# LockSwitchSchematicEasyEDA.net
KiCad netlist of a schematic drawn in EasyEDA
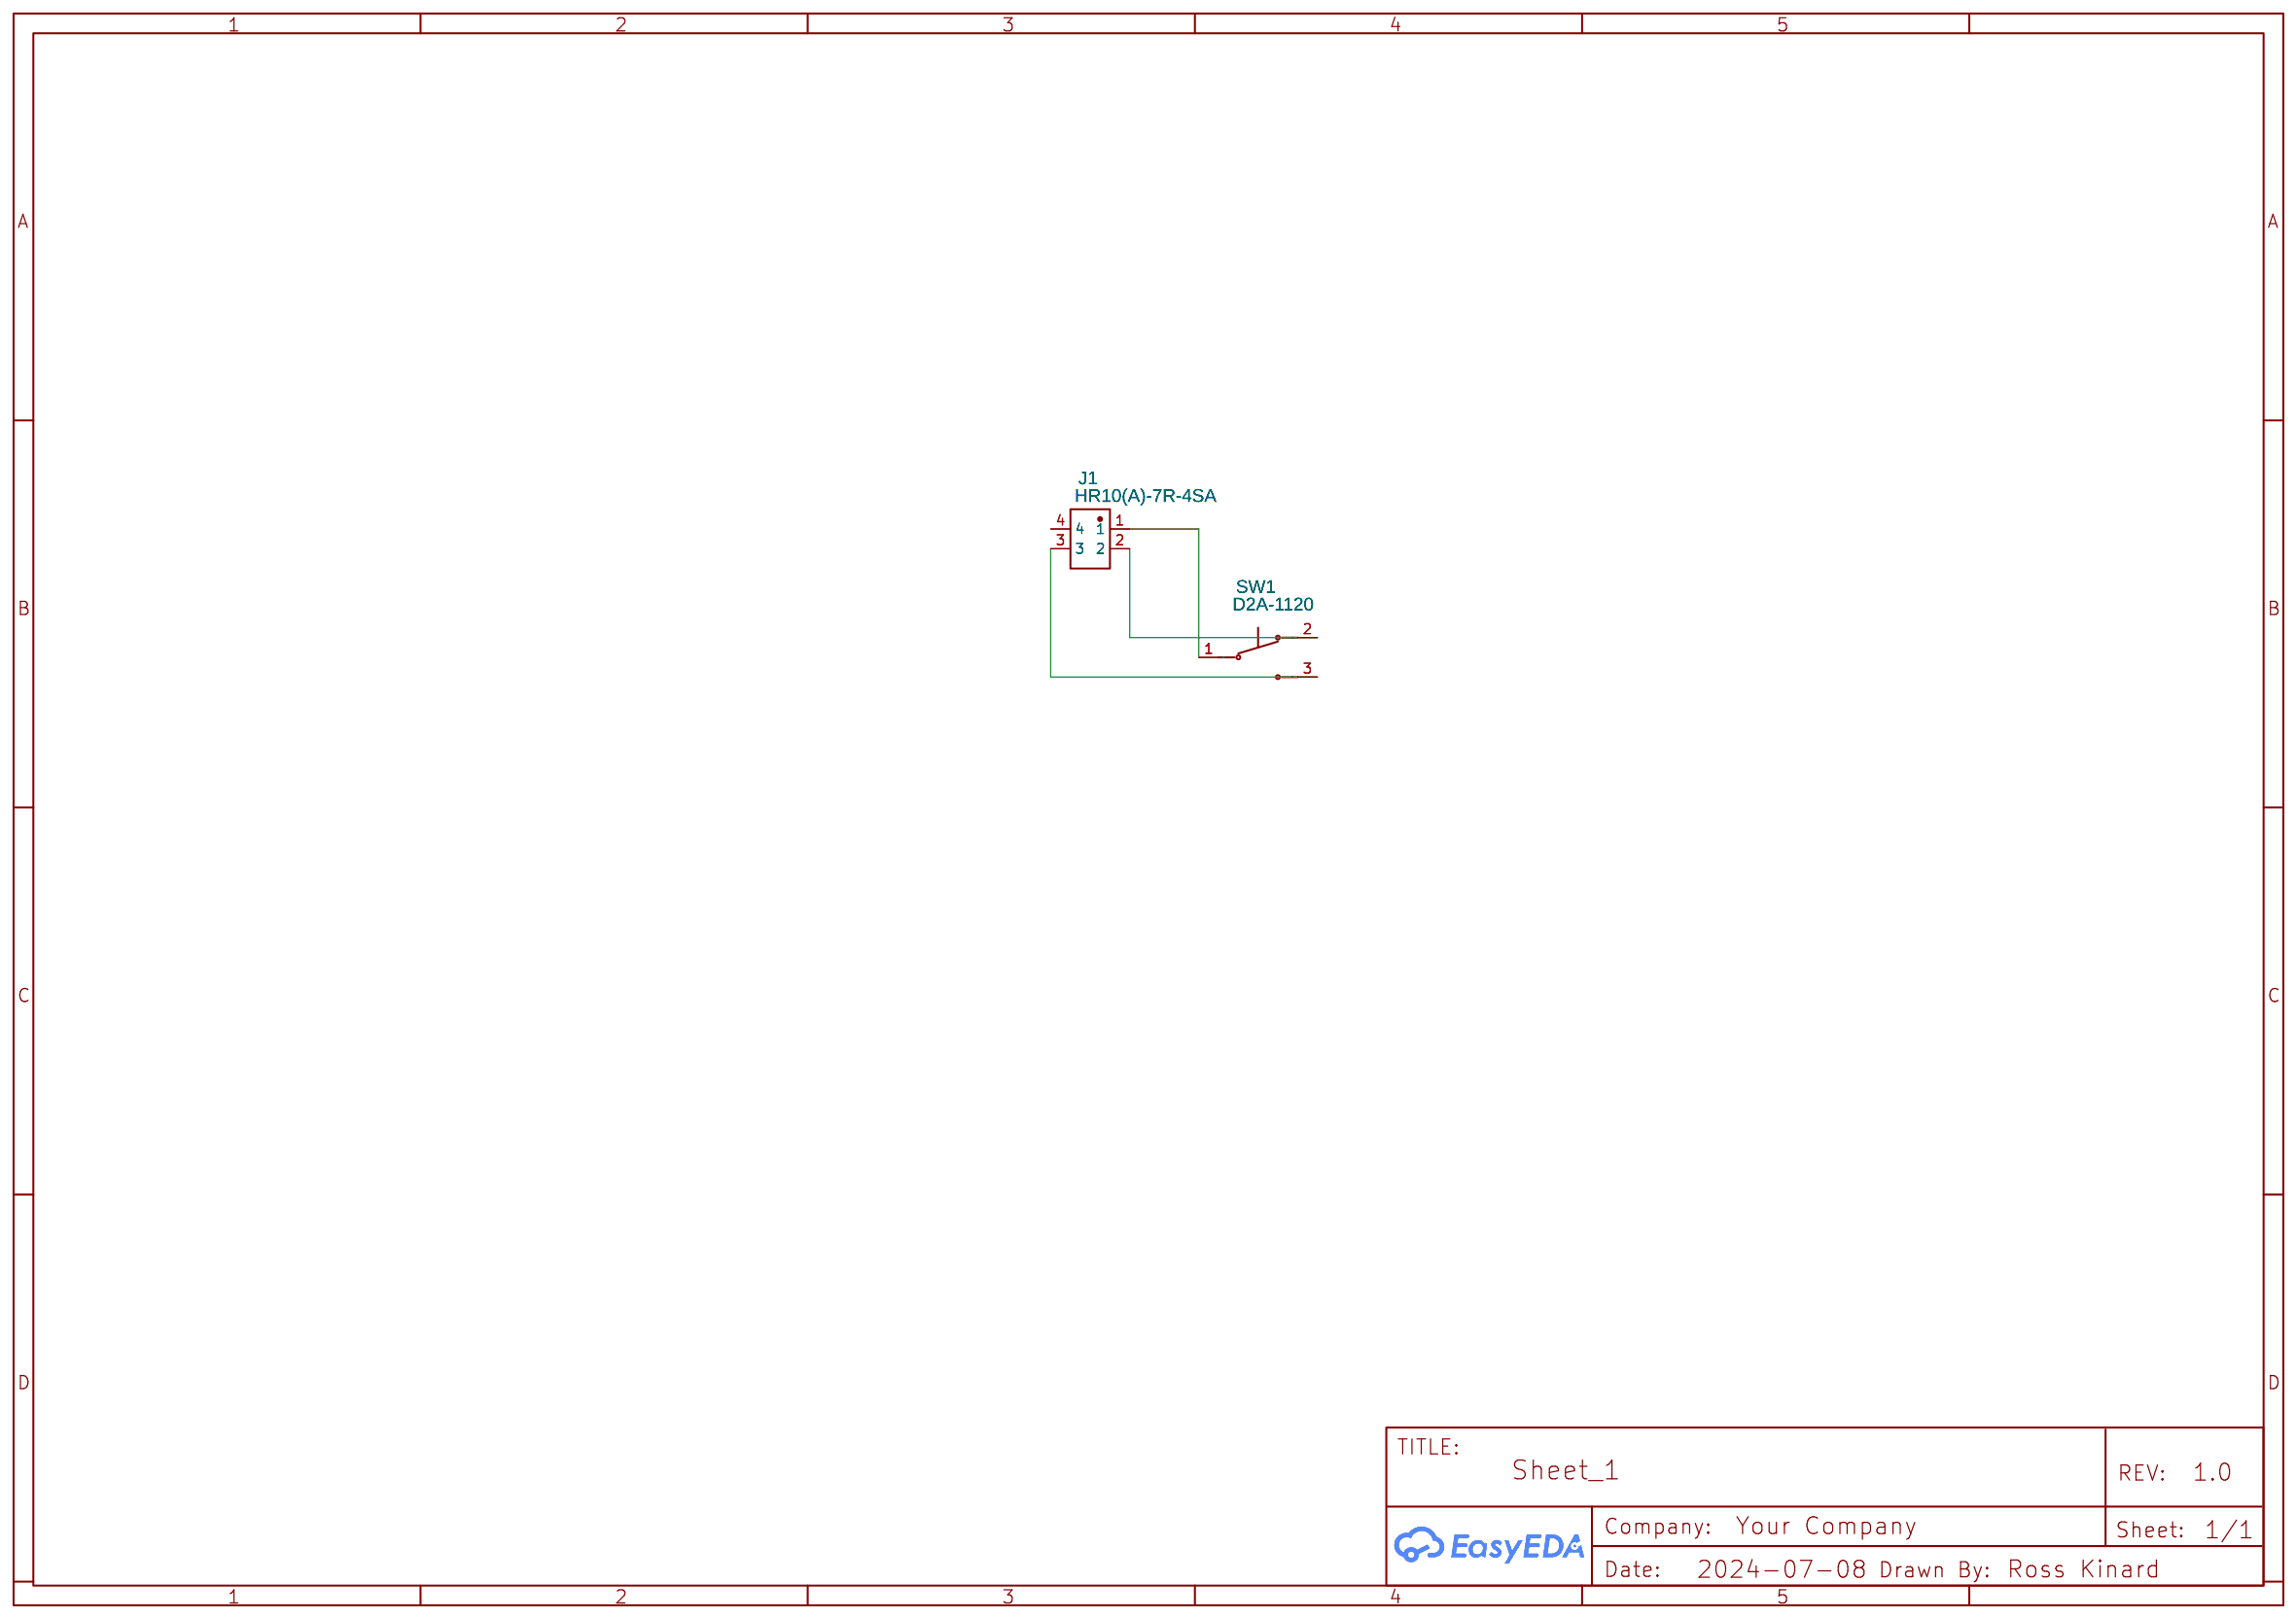
[diagram p0: schematic sheet]

(export (version "E")
  (design (tool "Eeschema 10.0.6"))
  (components
    (comp (ref "J1") (value "HR10(A)-7R-4SA") (libsource (lib "") (part "HR10(A)-7R-4SA")))
    (comp (ref "SW1")
      (value "D2A-1120")
      (fields (field (name "Manufacturer") "OMRON(欧姆龙)"))
      (libsource (lib "") (part "D2A-1120"))
    )
  )
  (nets
    (net (code "1") (name "Net-(SW1-COM)") (class "Default")
      (node (ref "J1") (pin "1") (pinfunction "1_1") (pintype "unspecified"))
      (node (ref "SW1") (pin "1") (pinfunction "COM_1") (pintype "unspecified"))
    )
    (net (code "2") (name "Net-(SW1-NC)") (class "Default")
      (node (ref "J1") (pin "2") (pinfunction "2_2") (pintype "unspecified"))
      (node (ref "SW1") (pin "2") (pinfunction "NC_2") (pintype "unspecified"))
    )
    (net (code "3") (name "Net-(SW1-NO)") (class "Default")
      (node (ref "J1") (pin "3") (pinfunction "3_3") (pintype "unspecified"))
      (node (ref "SW1") (pin "3") (pinfunction "NO_3") (pintype "unspecified"))
    )
    (net (code "4") (name "unconnected-(J1-Pad4)") (class "Default")
      (node (ref "J1") (pin "4") (pinfunction "4_4") (pintype "unspecified"))
    )
  )
)
